# CAN_3V3new.net
KiCad netlist of a schematic drawn in Altium Designer
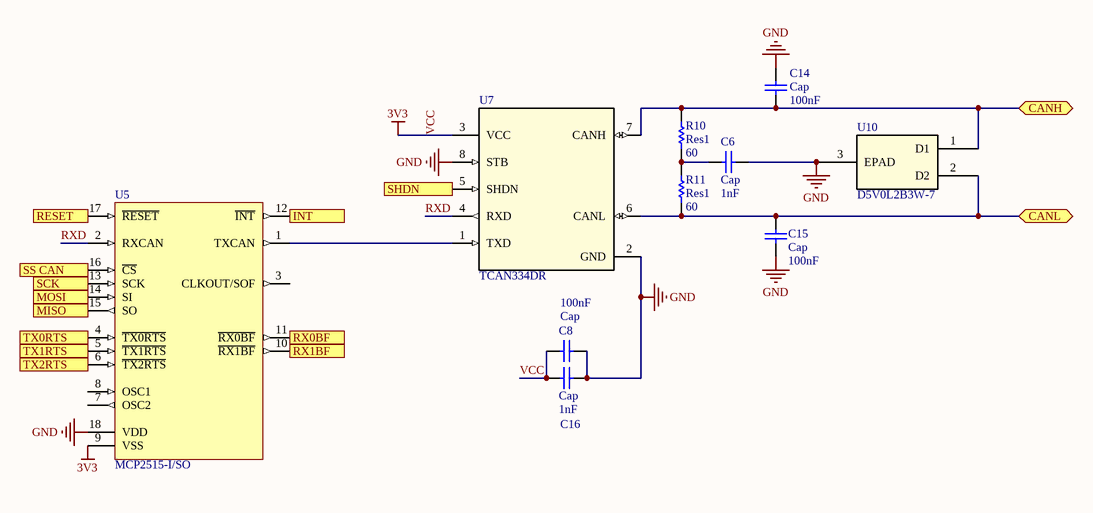
[diagram p0: CAN 3V3new.SchDoc]

(export (version "E")
  (design (tool "Eeschema 10.0.6"))
  (components
    (comp (ref "C6")
      (value "Cap")
      (footprint "1608[0603]")
      (description "Capacitor")
      (fields (field (name "ALTIUM_VALUE") "1nF") (field (name "PUBLISHER") "Altium Limited"))
      (libsource (lib "Miscellaneous Devices") (part "Cap"))
    )
    (comp (ref "C8")
      (value "Cap")
      (footprint "1608[0603]")
      (description "Capacitor")
      (fields (field (name "ALTIUM_VALUE") "100nF") (field (name "PUBLISHER") "Altium Limited"))
      (libsource (lib "Miscellaneous Devices") (part "Cap"))
    )
    (comp (ref "C14")
      (value "Cap")
      (footprint "1608[0603]")
      (description "Capacitor")
      (fields (field (name "ALTIUM_VALUE") "100nF") (field (name "PUBLISHER") "Altium Limited"))
      (libsource (lib "Miscellaneous Devices") (part "Cap"))
    )
    (comp (ref "C15")
      (value "Cap")
      (footprint "1608[0603]")
      (description "Capacitor")
      (fields (field (name "ALTIUM_VALUE") "100nF") (field (name "PUBLISHER") "Altium Limited"))
      (libsource (lib "Miscellaneous Devices") (part "Cap"))
    )
    (comp (ref "C16")
      (value "Cap")
      (footprint "1608[0603]")
      (description "Capacitor")
      (fields (field (name "ALTIUM_VALUE") "1nF") (field (name "PUBLISHER") "Altium Limited"))
      (libsource (lib "Miscellaneous Devices") (part "Cap"))
    )
    (comp (ref "R10")
      (value "Res1")
      (footprint "1608[0603]")
      (description "Resistor")
      (fields (field (name "ALTIUM_VALUE") "60") (field (name "PUBLISHER") "Altium Limited"))
      (libsource (lib "Miscellaneous Devices") (part "Res1"))
    )
    (comp (ref "R11")
      (value "Res1")
      (footprint "1608[0603]")
      (description "Resistor")
      (fields (field (name "ALTIUM_VALUE") "60") (field (name "PUBLISHER") "Altium Limited"))
      (libsource (lib "Miscellaneous Devices") (part "Res1"))
    )
    (comp (ref "U5")
      (value "MCP2515-I/SO")
      (footprint "SOIC-SO18_L")
      (description "Stand-Alone CAN Controller With SPI Interface, 18-Pin SOIC, Industrial Temperature")
      (libsource (lib "Altium Content Vault") (part "COM-CAN-MCP2515-18"))
    )
    (comp (ref "U7")
      (value "TCAN334DR")
      (footprint "D0008A_N")
      (description "No Description Available")
      (fields
        (field (name "MANUFACTURER") "Texas Instruments")
        (field (name "COPYRIGHT") "Copyright (C) 2018 Accelerated Designs. All rights reserved")
      )
      (libsource (lib "CANTRAN3V3") (part "TCAN334DR"))
    )
    (comp (ref "U10")
      (value "D5V0L2B3W-7")
      (footprint "SOT-323_DIO")
      (description "No Description Available")
      (fields (field (name "COPYRIGHT") "Copyright (C) 2018 Accelerated Designs. All rights reserved"))
      (libsource (lib "D5V0L2B3W-7 library") (part "D5V0L2B3W-7"))
    )
  )
  (nets
    (net (code "1") (name "/CANH") (class "Default")
      (node (ref "C14") (pin "2") (pinfunction "2_2") (pintype "passive"))
      (node (ref "R10") (pin "1") (pinfunction "1_1") (pintype "passive"))
      (node (ref "U10") (pin "1") (pinfunction "D1_1") (pintype "passive"))
      (node (ref "U7") (pin "7") (pinfunction "CANH_7") (pintype "bidirectional"))
    )
    (net (code "2") (name "/CANL") (class "Default")
      (node (ref "C15") (pin "2") (pinfunction "2_2") (pintype "passive"))
      (node (ref "R11") (pin "1") (pinfunction "1_1") (pintype "passive"))
      (node (ref "U10") (pin "2") (pinfunction "D2_2") (pintype "passive"))
      (node (ref "U7") (pin "6") (pinfunction "CANL_6") (pintype "bidirectional"))
    )
    (net (code "3") (name "/INT") (class "Default")
      (node (ref "U5") (pin "12") (pinfunction "~{INT}_12") (pintype "output"))
    )
    (net (code "4") (name "/MISO") (class "Default")
      (node (ref "U5") (pin "15") (pinfunction "SO_15") (pintype "output"))
    )
    (net (code "5") (name "/MOSI") (class "Default")
      (node (ref "U5") (pin "14") (pinfunction "SI_14") (pintype "input"))
    )
    (net (code "6") (name "/RESET") (class "Default")
      (node (ref "U5") (pin "17") (pinfunction "~{RESET}_17") (pintype "input"))
    )
    (net (code "7") (name "/RX0BF") (class "Default")
      (node (ref "U5") (pin "11") (pinfunction "~{RX0BF}_11") (pintype "output"))
    )
    (net (code "8") (name "/RX1BF") (class "Default")
      (node (ref "U5") (pin "10") (pinfunction "~{RX1BF}_10") (pintype "output"))
    )
    (net (code "9") (name "/RXD") (class "Default")
      (node (ref "U5") (pin "2") (pinfunction "RXCAN_2") (pintype "input"))
      (node (ref "U7") (pin "4") (pinfunction "RXD_4") (pintype "output"))
    )
    (net (code "10") (name "/SCK") (class "Default")
      (node (ref "U5") (pin "13") (pinfunction "SCK_13") (pintype "input"))
    )
    (net (code "11") (name "/SHDN") (class "Default")
      (node (ref "U7") (pin "5") (pinfunction "SHDN_5") (pintype "input"))
    )
    (net (code "12") (name "/SS CAN") (class "Default")
      (node (ref "U5") (pin "16") (pinfunction "~{CS}_16") (pintype "input"))
    )
    (net (code "13") (name "/TX0RTS") (class "Default")
      (node (ref "U5") (pin "4") (pinfunction "~{TX0RTS}_4") (pintype "input"))
    )
    (net (code "14") (name "/TX1RTS") (class "Default")
      (node (ref "U5") (pin "5") (pinfunction "~{TX1RTS}_5") (pintype "input"))
    )
    (net (code "15") (name "/TX2RTS") (class "Default")
      (node (ref "U5") (pin "6") (pinfunction "~{TX2RTS}_6") (pintype "input"))
    )
    (net (code "16") (name "3V3") (class "Default")
      (node (ref "C16") (pin "2") (pinfunction "2_2") (pintype "passive"))
      (node (ref "C8") (pin "1") (pinfunction "1_1") (pintype "passive"))
      (node (ref "U5") (pin "9") (pinfunction "VSS_9") (pintype "power_in"))
      (node (ref "U7") (pin "3") (pinfunction "VCC_3") (pintype "power_in"))
    )
    (net (code "17") (name "GND") (class "Default")
      (node (ref "C14") (pin "1") (pinfunction "1_1") (pintype "passive"))
      (node (ref "C15") (pin "1") (pinfunction "1_1") (pintype "passive"))
      (node (ref "C16") (pin "1") (pinfunction "1_1") (pintype "passive"))
      (node (ref "C6") (pin "2") (pinfunction "2_2") (pintype "passive"))
      (node (ref "C8") (pin "2") (pinfunction "2_2") (pintype "passive"))
      (node (ref "U10") (pin "3") (pinfunction "EPAD_3") (pintype "passive"))
      (node (ref "U5") (pin "18") (pinfunction "VDD_18") (pintype "power_in"))
      (node (ref "U7") (pin "2") (pinfunction "GND_2") (pintype "power_in"))
      (node (ref "U7") (pin "8") (pinfunction "STB_8") (pintype "input"))
    )
    (net (code "18") (name "Net-(C6-Pad1)") (class "Default")
      (node (ref "C6") (pin "1") (pinfunction "1_1") (pintype "passive"))
      (node (ref "R10") (pin "2") (pinfunction "2_2") (pintype "passive"))
      (node (ref "R11") (pin "2") (pinfunction "2_2") (pintype "passive"))
    )
    (net (code "19") (name "Net-(U5-TXCAN)") (class "Default")
      (node (ref "U5") (pin "1") (pinfunction "TXCAN_1") (pintype "output"))
      (node (ref "U7") (pin "1") (pinfunction "TXD_1") (pintype "input"))
    )
    (net (code "20") (name "unconnected-(U5-CLKOUT{slash}SOF-Pad3)") (class "Default")
      (node (ref "U5") (pin "3") (pinfunction "CLKOUT/SOF_3") (pintype "output"))
    )
    (net (code "21") (name "unconnected-(U5-OSC1-Pad8)") (class "Default")
      (node (ref "U5") (pin "8") (pinfunction "OSC1_8") (pintype "input"))
    )
    (net (code "22") (name "unconnected-(U5-OSC2-Pad7)") (class "Default")
      (node (ref "U5") (pin "7") (pinfunction "OSC2_7") (pintype "output"))
    )
  )
)
